# smart-switches.net
KiCad netlist of a schematic drawn in Altium Designer
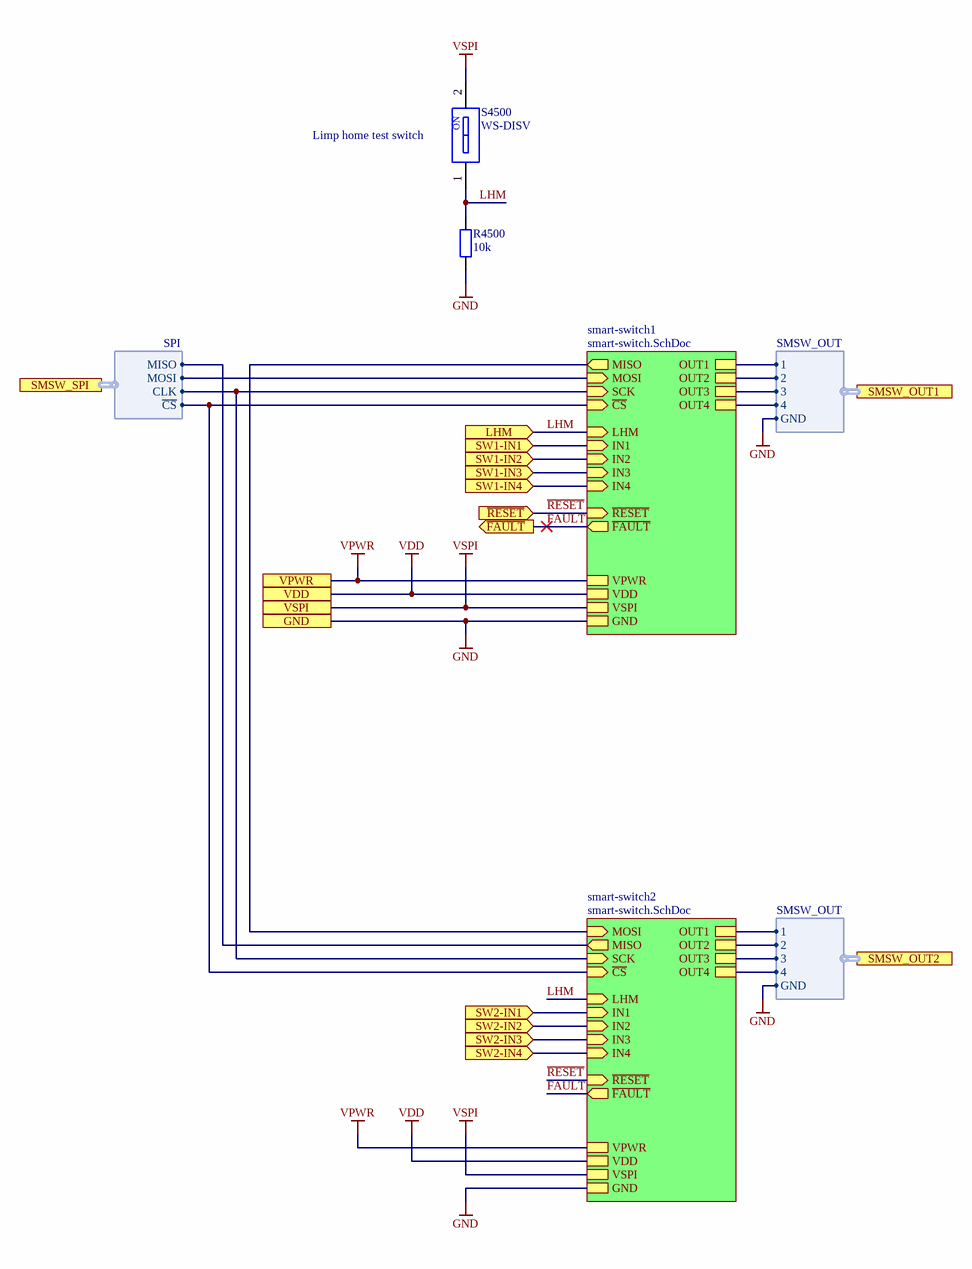
[diagram p0: smart-switches.SchDoc]

(export (version "E")
  (design (tool "Eeschema 10.0.6"))
  (components
    (comp (ref "R4500")
      (value "10k")
      (footprint "RESC1005X04N")
      (description "SMD Resistor 10k 0402")
      (fields (field (name "PART NUMBER") "gen_R_10k_0402") (field (name "TOLERANCE") "1%"))
      (libsource (lib "OE750") (part "R"))
    )
    (comp (ref "S4500")
      (value "WS-DISV")
      (footprint "WE_416131160801")
      (description "WS-DISV Small Compact SMT DipSwitch")
      (fields (field (name "PART NUMBER") "WE_416131160801") (field (name "MANUFACTURER") "Würth Elektronik"))
      (libsource (lib "OE750") (part "WE_416131160801"))
    )
  )
  (nets
    (net (code "5") (name "/LHM") (class "Default")
      (node (ref "R4500") (pin "2") (pinfunction "2_2") (pintype "passive"))
      (node (ref "S4500") (pin "1") (pinfunction "1_1") (pintype "passive"))
    )
    (net (code "29") (name "GND") (class "Default")
      (node (ref "R4500") (pin "1") (pinfunction "1_1") (pintype "passive"))
    )
    (net (code "32") (name "VSPI") (class "Default")
      (node (ref "S4500") (pin "2") (pinfunction "2_2") (pintype "passive"))
    )
  )
)
